# Connectors.net
KiCad netlist of a schematic drawn in Altium Designer
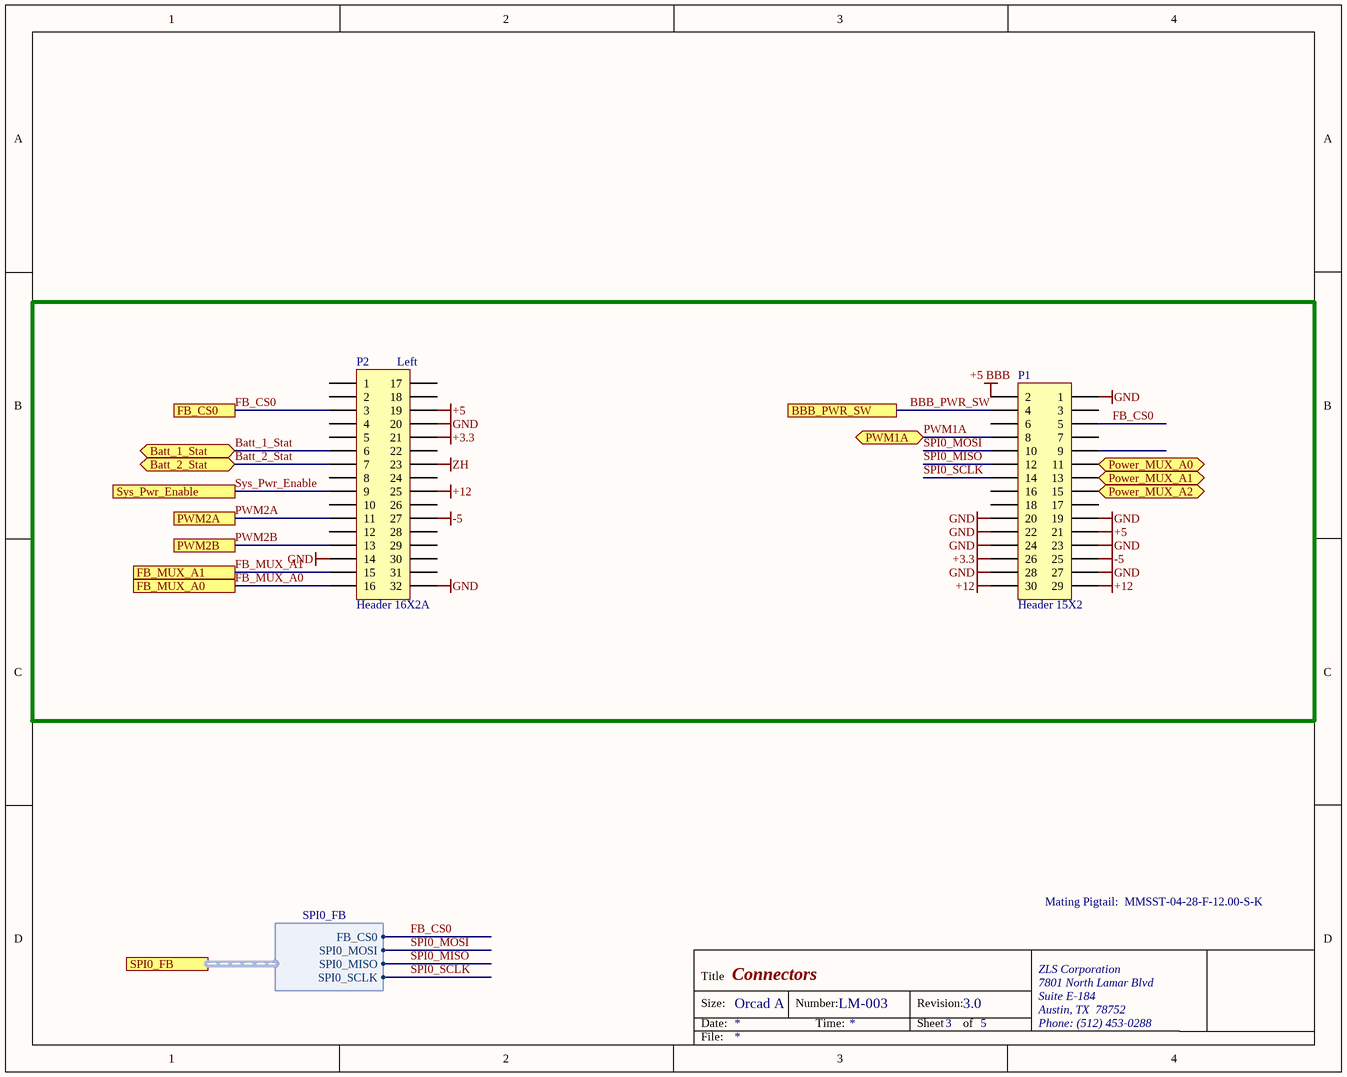
[diagram p0: Connectors.SchDoc]

(export (version "E")
  (design (tool "Eeschema 10.0.6"))
  (components
    (comp (ref "P1")
      (value "Header 15X2")
      (footprint "HDR2X15")
      (description "Header, 15-Pin, Dual row")
      (fields (field (name "PUBLISHER") "Altium Limited"))
      (libsource (lib "Miscellaneous Connectors") (part "Header 15X2"))
    )
    (comp (ref "P2")
      (value "Header 16X2A")
      (footprint "HDR2X16_CEN")
      (description "Header, 16-Pin, Dual row")
      (fields (field (name "PUBLISHER") "Altium Limited"))
      (libsource (lib "Miscellaneous Connectors") (part "Header 16X2A"))
    )
  )
  (nets
    (net (code "2") (name "+3.3") (class "Default")
      (node (ref "P1") (pin "26") (pinfunction "26_26") (pintype "passive"))
      (node (ref "P2") (pin "21") (pinfunction "21_21") (pintype "passive"))
    )
    (net (code "3") (name "+5") (class "Default")
      (node (ref "P1") (pin "21") (pinfunction "21_21") (pintype "passive"))
      (node (ref "P2") (pin "19") (pinfunction "19_19") (pintype "passive"))
    )
    (net (code "4") (name "+5 BBB") (class "Default")
      (node (ref "P1") (pin "2") (pinfunction "2_2") (pintype "passive"))
    )
    (net (code "5") (name "+12") (class "Default")
      (node (ref "P1") (pin "29") (pinfunction "29_29") (pintype "passive"))
      (node (ref "P1") (pin "30") (pinfunction "30_30") (pintype "passive"))
      (node (ref "P2") (pin "25") (pinfunction "25_25") (pintype "passive"))
    )
    (net (code "6") (name "-5") (class "Default")
      (node (ref "P1") (pin "25") (pinfunction "25_25") (pintype "passive"))
      (node (ref "P2") (pin "27") (pinfunction "27_27") (pintype "passive"))
    )
    (net (code "7") (name "/BBB_PWR_SW") (class "Default")
      (node (ref "P1") (pin "4") (pinfunction "4_4") (pintype "passive"))
    )
    (net (code "8") (name "/Batt_1_Stat") (class "Default")
      (node (ref "P2") (pin "6") (pinfunction "6_6") (pintype "passive"))
    )
    (net (code "9") (name "/Batt_2_Stat") (class "Default")
      (node (ref "P2") (pin "7") (pinfunction "7_7") (pintype "passive"))
    )
    (net (code "10") (name "/FB_CS0") (class "Default")
      (node (ref "P1") (pin "5") (pinfunction "5_5") (pintype "passive"))
      (node (ref "P2") (pin "3") (pinfunction "3_3") (pintype "passive"))
    )
    (net (code "11") (name "/FB_MUX_A0") (class "Default")
      (node (ref "P2") (pin "16") (pinfunction "16_16") (pintype "passive"))
    )
    (net (code "12") (name "/FB_MUX_A1") (class "Default")
      (node (ref "P2") (pin "15") (pinfunction "15_15") (pintype "passive"))
    )
    (net (code "13") (name "/PWM1A") (class "Default")
      (node (ref "P1") (pin "8") (pinfunction "8_8") (pintype "passive"))
    )
    (net (code "14") (name "/PWM2A") (class "Default")
      (node (ref "P2") (pin "11") (pinfunction "11_11") (pintype "passive"))
    )
    (net (code "15") (name "/PWM2B") (class "Default")
      (node (ref "P2") (pin "13") (pinfunction "13_13") (pintype "passive"))
    )
    (net (code "16") (name "/Power_MUX_A0") (class "Default")
      (node (ref "P1") (pin "11") (pinfunction "11_11") (pintype "passive"))
    )
    (net (code "17") (name "/Power_MUX_A1") (class "Default")
      (node (ref "P1") (pin "13") (pinfunction "13_13") (pintype "passive"))
    )
    (net (code "18") (name "/Power_MUX_A2") (class "Default")
      (node (ref "P1") (pin "15") (pinfunction "15_15") (pintype "passive"))
    )
    (net (code "19") (name "/SPI0_MISO") (class "Default")
      (node (ref "P1") (pin "12") (pinfunction "12_12") (pintype "passive"))
    )
    (net (code "20") (name "/SPI0_MOSI") (class "Default")
      (node (ref "P1") (pin "10") (pinfunction "10_10") (pintype "passive"))
    )
    (net (code "21") (name "/SPI0_SCLK") (class "Default")
      (node (ref "P1") (pin "14") (pinfunction "14_14") (pintype "passive"))
    )
    (net (code "22") (name "/Sys_Pwr_Enable") (class "Default")
      (node (ref "P2") (pin "9") (pinfunction "9_9") (pintype "passive"))
    )
    (net (code "24") (name "GND") (class "Default")
      (node (ref "P1") (pin "1") (pinfunction "1_1") (pintype "passive"))
      (node (ref "P1") (pin "19") (pinfunction "19_19") (pintype "passive"))
      (node (ref "P1") (pin "20") (pinfunction "20_20") (pintype "passive"))
      (node (ref "P1") (pin "22") (pinfunction "22_22") (pintype "passive"))
      (node (ref "P1") (pin "23") (pinfunction "23_23") (pintype "passive"))
      (node (ref "P1") (pin "24") (pinfunction "24_24") (pintype "passive"))
      (node (ref "P1") (pin "27") (pinfunction "27_27") (pintype "passive"))
      (node (ref "P1") (pin "28") (pinfunction "28_28") (pintype "passive"))
      (node (ref "P2") (pin "14") (pinfunction "14_14") (pintype "passive"))
      (node (ref "P2") (pin "20") (pinfunction "20_20") (pintype "passive"))
      (node (ref "P2") (pin "32") (pinfunction "32_32") (pintype "passive"))
    )
    (net (code "25") (name "ZH") (class "Default")
      (node (ref "P2") (pin "23") (pinfunction "23_23") (pintype "passive"))
    )
    (net (code "26") (name "unconnected-(P1-Pad3)") (class "Default")
      (node (ref "P1") (pin "3") (pinfunction "3_3") (pintype "passive"))
    )
    (net (code "27") (name "unconnected-(P1-Pad6)") (class "Default")
      (node (ref "P1") (pin "6") (pinfunction "6_6") (pintype "passive"))
    )
    (net (code "28") (name "unconnected-(P1-Pad7)") (class "Default")
      (node (ref "P1") (pin "7") (pinfunction "7_7") (pintype "passive"))
    )
    (net (code "29") (name "unconnected-(P1-Pad9)") (class "Default")
      (node (ref "P1") (pin "9") (pinfunction "9_9") (pintype "passive"))
    )
    (net (code "30") (name "unconnected-(P1-Pad16)") (class "Default")
      (node (ref "P1") (pin "16") (pinfunction "16_16") (pintype "passive"))
    )
    (net (code "31") (name "unconnected-(P1-Pad17)") (class "Default")
      (node (ref "P1") (pin "17") (pinfunction "17_17") (pintype "passive"))
    )
    (net (code "32") (name "unconnected-(P1-Pad18)") (class "Default")
      (node (ref "P1") (pin "18") (pinfunction "18_18") (pintype "passive"))
    )
    (net (code "33") (name "unconnected-(P2-Pad1)") (class "Default")
      (node (ref "P2") (pin "1") (pinfunction "1_1") (pintype "passive"))
    )
    (net (code "34") (name "unconnected-(P2-Pad2)") (class "Default")
      (node (ref "P2") (pin "2") (pinfunction "2_2") (pintype "passive"))
    )
    (net (code "35") (name "unconnected-(P2-Pad4)") (class "Default")
      (node (ref "P2") (pin "4") (pinfunction "4_4") (pintype "passive"))
    )
    (net (code "36") (name "unconnected-(P2-Pad5)") (class "Default")
      (node (ref "P2") (pin "5") (pinfunction "5_5") (pintype "passive"))
    )
    (net (code "37") (name "unconnected-(P2-Pad8)") (class "Default")
      (node (ref "P2") (pin "8") (pinfunction "8_8") (pintype "passive"))
    )
    (net (code "38") (name "unconnected-(P2-Pad10)") (class "Default")
      (node (ref "P2") (pin "10") (pinfunction "10_10") (pintype "passive"))
    )
    (net (code "39") (name "unconnected-(P2-Pad12)") (class "Default")
      (node (ref "P2") (pin "12") (pinfunction "12_12") (pintype "passive"))
    )
    (net (code "40") (name "unconnected-(P2-Pad17)") (class "Default")
      (node (ref "P2") (pin "17") (pinfunction "17_17") (pintype "passive"))
    )
    (net (code "41") (name "unconnected-(P2-Pad18)") (class "Default")
      (node (ref "P2") (pin "18") (pinfunction "18_18") (pintype "passive"))
    )
    (net (code "42") (name "unconnected-(P2-Pad22)") (class "Default")
      (node (ref "P2") (pin "22") (pinfunction "22_22") (pintype "passive"))
    )
    (net (code "43") (name "unconnected-(P2-Pad24)") (class "Default")
      (node (ref "P2") (pin "24") (pinfunction "24_24") (pintype "passive"))
    )
    (net (code "44") (name "unconnected-(P2-Pad26)") (class "Default")
      (node (ref "P2") (pin "26") (pinfunction "26_26") (pintype "passive"))
    )
    (net (code "45") (name "unconnected-(P2-Pad28)") (class "Default")
      (node (ref "P2") (pin "28") (pinfunction "28_28") (pintype "passive"))
    )
    (net (code "46") (name "unconnected-(P2-Pad29)") (class "Default")
      (node (ref "P2") (pin "29") (pinfunction "29_29") (pintype "passive"))
    )
    (net (code "47") (name "unconnected-(P2-Pad30)") (class "Default")
      (node (ref "P2") (pin "30") (pinfunction "30_30") (pintype "passive"))
    )
    (net (code "48") (name "unconnected-(P2-Pad31)") (class "Default")
      (node (ref "P2") (pin "31") (pinfunction "31_31") (pintype "passive"))
    )
  )
)
